# cvocd-a.net
KiCad netlist of a schematic drawn in EAGLE
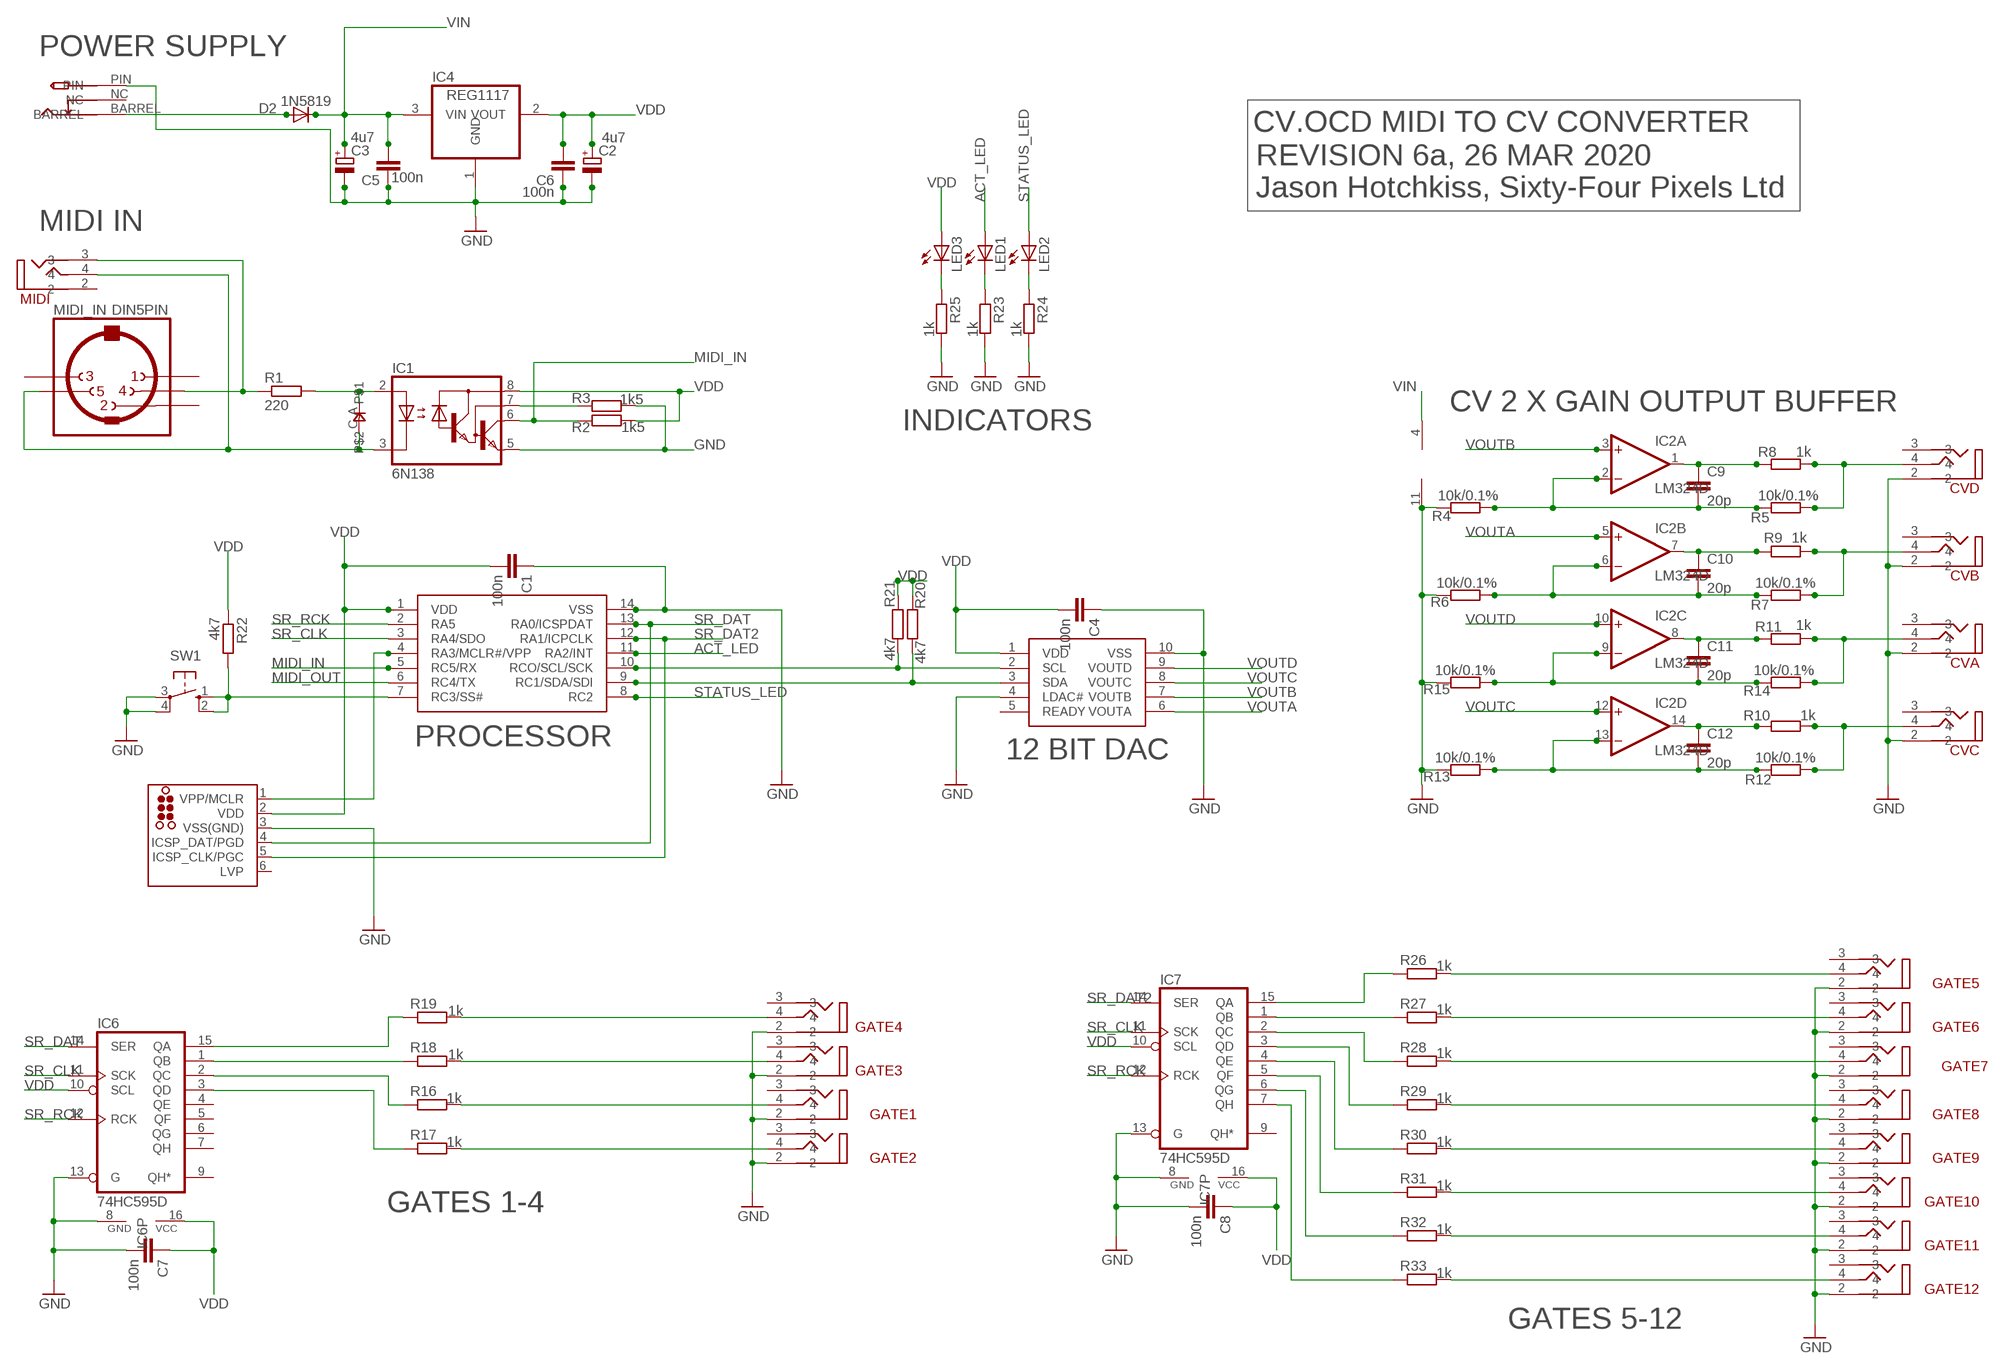
[diagram p0: schematic, sheet 1]

(export (version "E")
  (design (tool "Eeschema 10.0.6"))
  (components
    (comp (ref "C1")
      (value "100n")
      (footprint "eagle-import:C0805")
      (libsource (lib "eagle-import") (part "C-EUC0805"))
    )
    (comp (ref "C2")
      (value "4u7")
      (footprint "eagle-import:PANASONIC_C")
      (libsource (lib "eagle-import") (part "CPOL-EUC"))
    )
    (comp (ref "C3")
      (value "4u7")
      (footprint "eagle-import:PANASONIC_C")
      (libsource (lib "eagle-import") (part "CPOL-EUC"))
    )
    (comp (ref "C4")
      (value "100n")
      (footprint "eagle-import:C0805")
      (libsource (lib "eagle-import") (part "C-EUC0805"))
    )
    (comp (ref "C5")
      (value "100n")
      (footprint "eagle-import:C0805")
      (libsource (lib "eagle-import") (part "C-EUC0805"))
    )
    (comp (ref "C6")
      (value "100n")
      (footprint "eagle-import:C0805")
      (libsource (lib "eagle-import") (part "C-EUC0805"))
    )
    (comp (ref "C7")
      (value "100n")
      (footprint "eagle-import:C0805")
      (libsource (lib "eagle-import") (part "C-EUC0805"))
    )
    (comp (ref "C8")
      (value "100n")
      (footprint "eagle-import:C0805")
      (libsource (lib "eagle-import") (part "C-EUC0805"))
    )
    (comp (ref "C9")
      (value "20p")
      (footprint "eagle-import:C0805")
      (libsource (lib "eagle-import") (part "C-EUC0805"))
    )
    (comp (ref "C10")
      (value "20p")
      (footprint "eagle-import:C0805")
      (libsource (lib "eagle-import") (part "C-EUC0805"))
    )
    (comp (ref "C11")
      (value "20p")
      (footprint "eagle-import:C0805")
      (libsource (lib "eagle-import") (part "C-EUC0805"))
    )
    (comp (ref "C12")
      (value "20p")
      (footprint "eagle-import:C0805")
      (libsource (lib "eagle-import") (part "C-EUC0805"))
    )
    (comp (ref "CVA")
      (value "VERTICAL_3_5MM_SOCKET")
      (footprint "eagle-import:VERTICAL_3_5MM_SOCKET")
      (libsource (lib "eagle-import") (part "VERTICAL_3_5MM_SOCKET"))
    )
    (comp (ref "CVB")
      (value "VERTICAL_3_5MM_SOCKET")
      (footprint "eagle-import:VERTICAL_3_5MM_SOCKET")
      (libsource (lib "eagle-import") (part "VERTICAL_3_5MM_SOCKET"))
    )
    (comp (ref "CVC")
      (value "VERTICAL_3_5MM_SOCKET")
      (footprint "eagle-import:VERTICAL_3_5MM_SOCKET")
      (libsource (lib "eagle-import") (part "VERTICAL_3_5MM_SOCKET"))
    )
    (comp (ref "CVD")
      (value "VERTICAL_3_5MM_SOCKET")
      (footprint "eagle-import:VERTICAL_3_5MM_SOCKET")
      (libsource (lib "eagle-import") (part "VERTICAL_3_5MM_SOCKET"))
    )
    (comp (ref "D1")
      (value "0805DIODE")
      (footprint "eagle-import:0805DIODE")
      (libsource (lib "eagle-import") (part "0805DIODE"))
    )
    (comp (ref "D2")
      (value "1N5819")
      (footprint "eagle-import:SOD123")
      (libsource (lib "eagle-import") (part "DIODE-SOD123"))
    )
    (comp (ref "GATE1")
      (value "VERTICAL_3_5MM_SOCKET")
      (footprint "eagle-import:VERTICAL_3_5MM_SOCKET")
      (libsource (lib "eagle-import") (part "VERTICAL_3_5MM_SOCKET"))
    )
    (comp (ref "GATE2")
      (value "VERTICAL_3_5MM_SOCKET")
      (footprint "eagle-import:VERTICAL_3_5MM_SOCKET")
      (libsource (lib "eagle-import") (part "VERTICAL_3_5MM_SOCKET"))
    )
    (comp (ref "GATE3")
      (value "VERTICAL_3_5MM_SOCKET")
      (footprint "eagle-import:VERTICAL_3_5MM_SOCKET")
      (libsource (lib "eagle-import") (part "VERTICAL_3_5MM_SOCKET"))
    )
    (comp (ref "GATE4")
      (value "VERTICAL_3_5MM_SOCKET")
      (footprint "eagle-import:VERTICAL_3_5MM_SOCKET")
      (libsource (lib "eagle-import") (part "VERTICAL_3_5MM_SOCKET"))
    )
    (comp (ref "GATE5")
      (value "VERTICAL_3_5MM_SOCKET")
      (footprint "eagle-import:VERTICAL_3_5MM_SOCKET")
      (libsource (lib "eagle-import") (part "VERTICAL_3_5MM_SOCKET"))
    )
    (comp (ref "GATE6")
      (value "VERTICAL_3_5MM_SOCKET")
      (footprint "eagle-import:VERTICAL_3_5MM_SOCKET")
      (libsource (lib "eagle-import") (part "VERTICAL_3_5MM_SOCKET"))
    )
    (comp (ref "GATE7")
      (value "VERTICAL_3_5MM_SOCKET")
      (footprint "eagle-import:VERTICAL_3_5MM_SOCKET")
      (libsource (lib "eagle-import") (part "VERTICAL_3_5MM_SOCKET"))
    )
    (comp (ref "GATE8")
      (value "VERTICAL_3_5MM_SOCKET")
      (footprint "eagle-import:VERTICAL_3_5MM_SOCKET")
      (libsource (lib "eagle-import") (part "VERTICAL_3_5MM_SOCKET"))
    )
    (comp (ref "GATE9")
      (value "VERTICAL_3_5MM_SOCKET")
      (footprint "eagle-import:VERTICAL_3_5MM_SOCKET")
      (libsource (lib "eagle-import") (part "VERTICAL_3_5MM_SOCKET"))
    )
    (comp (ref "GATE10")
      (value "VERTICAL_3_5MM_SOCKET")
      (footprint "eagle-import:VERTICAL_3_5MM_SOCKET")
      (libsource (lib "eagle-import") (part "VERTICAL_3_5MM_SOCKET"))
    )
    (comp (ref "GATE11")
      (value "VERTICAL_3_5MM_SOCKET")
      (footprint "eagle-import:VERTICAL_3_5MM_SOCKET")
      (libsource (lib "eagle-import") (part "VERTICAL_3_5MM_SOCKET"))
    )
    (comp (ref "GATE12")
      (value "VERTICAL_3_5MM_SOCKET")
      (footprint "eagle-import:VERTICAL_3_5MM_SOCKET")
      (libsource (lib "eagle-import") (part "VERTICAL_3_5MM_SOCKET"))
    )
    (comp (ref "IC1")
      (value "6N138")
      (footprint "eagle-import:DIL08")
      (fields (field (name "MF") "VISHAY/TELEFUNKEN"))
      (libsource (lib "eagle-import") (part "6N138"))
    )
    (comp (ref "IC2")
      (value "LM324D")
      (footprint "eagle-import:SO14")
      (libsource (lib "eagle-import") (part "LM324D"))
    )
    (comp (ref "IC3")
      (value "MCP4728_QUAD_DAC")
      (footprint "eagle-import:MSOP10")
      (libsource (lib "eagle-import") (part "MCP4728_QUAD_DAC"))
    )
    (comp (ref "IC4")
      (value "REG1117")
      (footprint "eagle-import:SOT223")
      (libsource (lib "eagle-import") (part "REG1117"))
    )
    (comp (ref "IC5")
      (value "PIC16F1825SO14")
      (footprint "eagle-import:SO14")
      (libsource (lib "eagle-import") (part "PIC16F1825SO14"))
    )
    (comp (ref "IC6")
      (value "74HC595D")
      (footprint "eagle-import:SO16")
      (libsource (lib "eagle-import") (part "74595DHC"))
    )
    (comp (ref "IC7")
      (value "74HC595D")
      (footprint "eagle-import:SO16")
      (libsource (lib "eagle-import") (part "74595DHC"))
    )
    (comp (ref "ICSP")
      (value "TC2030-MCP-NL")
      (footprint "eagle-import:TC2030-MCP-NL")
      (libsource (lib "eagle-import") (part "TC2030-MCP-NL"))
    )
    (comp (ref "LED1")
      (value "LED3MM")
      (footprint "eagle-import:LED3MM")
      (libsource (lib "eagle-import") (part "LED3MM"))
    )
    (comp (ref "LED2")
      (value "LED3MM")
      (footprint "eagle-import:LED3MM")
      (libsource (lib "eagle-import") (part "LED3MM"))
    )
    (comp (ref "LED3")
      (value "LED3MM")
      (footprint "eagle-import:LED3MM")
      (libsource (lib "eagle-import") (part "LED3MM"))
    )
    (comp (ref "MIDI")
      (value "VERTICAL_3_5MM_SOCKET")
      (footprint "eagle-import:VERTICAL_3_5MM_SOCKET")
      (libsource (lib "eagle-import") (part "VERTICAL_3_5MM_SOCKET"))
    )
    (comp (ref "MIDI_IN")
      (value "DIN5PIN")
      (footprint "eagle-import:EDGEDIN")
      (libsource (lib "eagle-import") (part "DIN5PIN"))
    )
    (comp (ref "R1")
      (value "220")
      (footprint "eagle-import:R0805")
      (libsource (lib "eagle-import") (part "R-EU_R0805"))
    )
    (comp (ref "R2")
      (value "1k5")
      (footprint "eagle-import:R0805")
      (libsource (lib "eagle-import") (part "R-EU_R0805"))
    )
    (comp (ref "R3")
      (value "1k5")
      (footprint "eagle-import:R0805")
      (libsource (lib "eagle-import") (part "R-EU_R0805"))
    )
    (comp (ref "R4")
      (value "10k/0.1%")
      (footprint "eagle-import:R0805")
      (libsource (lib "eagle-import") (part "R-EU_R0805"))
    )
    (comp (ref "R5")
      (value "10k/0.1%")
      (footprint "eagle-import:R0805")
      (libsource (lib "eagle-import") (part "R-EU_R0805"))
    )
    (comp (ref "R6")
      (value "10k/0.1%")
      (footprint "eagle-import:R0805")
      (libsource (lib "eagle-import") (part "R-EU_R0805"))
    )
    (comp (ref "R7")
      (value "10k/0.1%")
      (footprint "eagle-import:R0805")
      (libsource (lib "eagle-import") (part "R-EU_R0805"))
    )
    (comp (ref "R8")
      (value "1k")
      (footprint "eagle-import:R0805")
      (libsource (lib "eagle-import") (part "R-EU_R0805"))
    )
    (comp (ref "R9")
      (value "1k")
      (footprint "eagle-import:R0805")
      (libsource (lib "eagle-import") (part "R-EU_R0805"))
    )
    (comp (ref "R10")
      (value "1k")
      (footprint "eagle-import:R0805")
      (libsource (lib "eagle-import") (part "R-EU_R0805"))
    )
    (comp (ref "R11")
      (value "1k")
      (footprint "eagle-import:R0805")
      (libsource (lib "eagle-import") (part "R-EU_R0805"))
    )
    (comp (ref "R12")
      (value "10k/0.1%")
      (footprint "eagle-import:R0805")
      (libsource (lib "eagle-import") (part "R-EU_R0805"))
    )
    (comp (ref "R13")
      (value "10k/0.1%")
      (footprint "eagle-import:R0805")
      (libsource (lib "eagle-import") (part "R-EU_R0805"))
    )
    (comp (ref "R14")
      (value "10k/0.1%")
      (footprint "eagle-import:R0805")
      (libsource (lib "eagle-import") (part "R-EU_R0805"))
    )
    (comp (ref "R15")
      (value "10k/0.1%")
      (footprint "eagle-import:R0805")
      (libsource (lib "eagle-import") (part "R-EU_R0805"))
    )
    (comp (ref "R16")
      (value "1k")
      (footprint "eagle-import:R0805")
      (libsource (lib "eagle-import") (part "R-EU_R0805"))
    )
    (comp (ref "R17")
      (value "1k")
      (footprint "eagle-import:R0805")
      (libsource (lib "eagle-import") (part "R-EU_R0805"))
    )
    (comp (ref "R18")
      (value "1k")
      (footprint "eagle-import:R0805")
      (libsource (lib "eagle-import") (part "R-EU_R0805"))
    )
    (comp (ref "R19")
      (value "1k")
      (footprint "eagle-import:R0805")
      (libsource (lib "eagle-import") (part "R-EU_R0805"))
    )
    (comp (ref "R20")
      (value "4k7")
      (footprint "eagle-import:R0805")
      (libsource (lib "eagle-import") (part "R-EU_R0805"))
    )
    (comp (ref "R21")
      (value "4k7")
      (footprint "eagle-import:R0805")
      (libsource (lib "eagle-import") (part "R-EU_R0805"))
    )
    (comp (ref "R22")
      (value "4k7")
      (footprint "eagle-import:R0805")
      (libsource (lib "eagle-import") (part "R-EU_R0805"))
    )
    (comp (ref "R23")
      (value "1k")
      (footprint "eagle-import:R0805")
      (libsource (lib "eagle-import") (part "R-EU_R0805"))
    )
    (comp (ref "R24")
      (value "1k")
      (footprint "eagle-import:R0805")
      (libsource (lib "eagle-import") (part "R-EU_R0805"))
    )
    (comp (ref "R25")
      (value "1k")
      (footprint "eagle-import:R0805")
      (libsource (lib "eagle-import") (part "R-EU_R0805"))
    )
    (comp (ref "R26")
      (value "1k")
      (footprint "eagle-import:R0805")
      (libsource (lib "eagle-import") (part "R-EU_R0805"))
    )
    (comp (ref "R27")
      (value "1k")
      (footprint "eagle-import:R0805")
      (libsource (lib "eagle-import") (part "R-EU_R0805"))
    )
    (comp (ref "R28")
      (value "1k")
      (footprint "eagle-import:R0805")
      (libsource (lib "eagle-import") (part "R-EU_R0805"))
    )
    (comp (ref "R29")
      (value "1k")
      (footprint "eagle-import:R0805")
      (libsource (lib "eagle-import") (part "R-EU_R0805"))
    )
    (comp (ref "R30")
      (value "1k")
      (footprint "eagle-import:R0805")
      (libsource (lib "eagle-import") (part "R-EU_R0805"))
    )
    (comp (ref "R31")
      (value "1k")
      (footprint "eagle-import:R0805")
      (libsource (lib "eagle-import") (part "R-EU_R0805"))
    )
    (comp (ref "R32")
      (value "1k")
      (footprint "eagle-import:R0805")
      (libsource (lib "eagle-import") (part "R-EU_R0805"))
    )
    (comp (ref "R33")
      (value "1k")
      (footprint "eagle-import:R0805")
      (libsource (lib "eagle-import") (part "R-EU_R0805"))
    )
    (comp (ref "SW1")
      (value "10-XX")
      (footprint "eagle-import:B3F-10XX")
      (fields (field (name "MPN") "B3F-1000"))
      (libsource (lib "eagle-import") (part "10-XX"))
    )
    (comp (ref "U$2")
      (value "PWR_SOCKET_2_1MM")
      (footprint "eagle-import:PWR_SOCKET_2_1MM")
      (libsource (lib "eagle-import") (part "PWR_SOCKET_2_1MM"))
    )
  )
  (nets
    (net (code "1") (name "/ACT_LED") (class "Default")
      (node (ref "IC5") (pin "11") (pinfunction "RA2/INT_11") (pintype "bidirectional"))
      (node (ref "LED1") (pin "A") (pinfunction "A_A") (pintype "passive"))
    )
    (net (code "2") (name "/MIDI_IN") (class "Default")
      (node (ref "IC1") (pin "6") (pinfunction "VO_6") (pintype "passive"))
      (node (ref "IC5") (pin "5") (pinfunction "RC5/RX_5") (pintype "bidirectional"))
      (node (ref "R2") (pin "1") (pinfunction "1_1") (pintype "passive"))
    )
    (net (code "3") (name "/MIDI_OUT") (class "Default")
      (node (ref "IC5") (pin "6") (pinfunction "RC4/TX_6") (pintype "bidirectional"))
    )
    (net (code "4") (name "/SR_CLK") (class "Default")
      (node (ref "IC5") (pin "3") (pinfunction "RA4/SDO_3") (pintype "bidirectional"))
      (node (ref "IC6") (pin "11") (pinfunction "SCK_11") (pintype "input"))
      (node (ref "IC7") (pin "11") (pinfunction "SCK_11") (pintype "input"))
    )
    (net (code "5") (name "/SR_DAT") (class "Default")
      (node (ref "IC5") (pin "13") (pinfunction "RA0/ICSPDAT_13") (pintype "bidirectional"))
      (node (ref "IC6") (pin "14") (pinfunction "SER_14") (pintype "input"))
      (node (ref "ICSP") (pin "4") (pinfunction "ICSP_DAT/PGD_4") (pintype "bidirectional"))
    )
    (net (code "6") (name "/SR_DAT2") (class "Default")
      (node (ref "IC5") (pin "12") (pinfunction "RA1/ICPCLK_12") (pintype "bidirectional"))
      (node (ref "IC7") (pin "14") (pinfunction "SER_14") (pintype "input"))
      (node (ref "ICSP") (pin "5") (pinfunction "ICSP_CLK/PGC_5") (pintype "output"))
    )
    (net (code "7") (name "/SR_RCK") (class "Default")
      (node (ref "IC5") (pin "2") (pinfunction "RA5_2") (pintype "bidirectional"))
      (node (ref "IC6") (pin "12") (pinfunction "RCK_12") (pintype "input"))
      (node (ref "IC7") (pin "12") (pinfunction "RCK_12") (pintype "input"))
    )
    (net (code "8") (name "/STATUS_LED") (class "Default")
      (node (ref "IC5") (pin "8") (pinfunction "RC2_8") (pintype "bidirectional"))
      (node (ref "LED2") (pin "A") (pinfunction "A_A") (pintype "passive"))
    )
    (net (code "9") (name "/VDD") (class "Default")
      (node (ref "C1") (pin "2") (pinfunction "2_2") (pintype "passive"))
      (node (ref "C2") (pin "+") (pinfunction "+_+") (pintype "passive"))
      (node (ref "C4") (pin "2") (pinfunction "2_2") (pintype "passive"))
      (node (ref "C6") (pin "2") (pinfunction "2_2") (pintype "passive"))
      (node (ref "C7") (pin "1") (pinfunction "1_1") (pintype "passive"))
      (node (ref "C8") (pin "1") (pinfunction "1_1") (pintype "passive"))
      (node (ref "IC1") (pin "8") (pinfunction "VCC_8") (pintype "passive"))
      (node (ref "IC3") (pin "1") (pinfunction "VDD_1") (pintype "power_in"))
      (node (ref "IC4") (pin "2") (pinfunction "VOUT_2") (pintype "output"))
      (node (ref "IC5") (pin "1") (pinfunction "VDD_1") (pintype "power_in"))
      (node (ref "IC6") (pin "10") (pinfunction "SCL_10") (pintype "input"))
      (node (ref "IC6") (pin "16") (pinfunction "VCC_16") (pintype "power_in"))
      (node (ref "IC7") (pin "10") (pinfunction "SCL_10") (pintype "input"))
      (node (ref "IC7") (pin "16") (pinfunction "VCC_16") (pintype "power_in"))
      (node (ref "ICSP") (pin "2") (pinfunction "VDD_2") (pintype "power_in"))
      (node (ref "LED3") (pin "A") (pinfunction "A_A") (pintype "passive"))
      (node (ref "R2") (pin "2") (pinfunction "2_2") (pintype "passive"))
      (node (ref "R20") (pin "1") (pinfunction "1_1") (pintype "passive"))
      (node (ref "R21") (pin "1") (pinfunction "1_1") (pintype "passive"))
      (node (ref "R22") (pin "1") (pinfunction "1_1") (pintype "passive"))
    )
    (net (code "10") (name "/VIN") (class "Default")
      (node (ref "C3") (pin "+") (pinfunction "+_+") (pintype "passive"))
      (node (ref "C5") (pin "2") (pinfunction "2_2") (pintype "passive"))
      (node (ref "D2") (pin "C") (pinfunction "C_C") (pintype "passive"))
      (node (ref "IC2") (pin "4") (pinfunction "V+_4") (pintype "power_in"))
      (node (ref "IC4") (pin "3") (pinfunction "VIN_3") (pintype "input"))
    )
    (net (code "11") (name "/VOUTA") (class "Default")
      (node (ref "IC2") (pin "5") (pinfunction "+IN_5") (pintype "input"))
      (node (ref "IC3") (pin "6") (pinfunction "VOUTA_6") (pintype "bidirectional"))
    )
    (net (code "12") (name "/VOUTB") (class "Default")
      (node (ref "IC2") (pin "3") (pinfunction "+IN_3") (pintype "input"))
      (node (ref "IC3") (pin "7") (pinfunction "VOUTB_7") (pintype "bidirectional"))
    )
    (net (code "13") (name "/VOUTC") (class "Default")
      (node (ref "IC2") (pin "12") (pinfunction "+IN_12") (pintype "input"))
      (node (ref "IC3") (pin "8") (pinfunction "VOUTC_8") (pintype "bidirectional"))
    )
    (net (code "14") (name "/VOUTD") (class "Default")
      (node (ref "IC2") (pin "10") (pinfunction "+IN_10") (pintype "input"))
      (node (ref "IC3") (pin "9") (pinfunction "VOUTD_9") (pintype "bidirectional"))
    )
    (net (code "15") (name "GND") (class "Default")
      (node (ref "C1") (pin "1") (pinfunction "1_1") (pintype "passive"))
      (node (ref "C2") (pin "-") (pinfunction "-_-") (pintype "passive"))
      (node (ref "C3") (pin "-") (pinfunction "-_-") (pintype "passive"))
      (node (ref "C4") (pin "1") (pinfunction "1_1") (pintype "passive"))
      (node (ref "C5") (pin "1") (pinfunction "1_1") (pintype "passive"))
      (node (ref "C6") (pin "1") (pinfunction "1_1") (pintype "passive"))
      (node (ref "C7") (pin "2") (pinfunction "2_2") (pintype "passive"))
      (node (ref "C8") (pin "2") (pinfunction "2_2") (pintype "passive"))
      (node (ref "CVA") (pin "2") (pinfunction "2_2") (pintype "bidirectional"))
      (node (ref "CVB") (pin "2") (pinfunction "2_2") (pintype "bidirectional"))
      (node (ref "CVC") (pin "2") (pinfunction "2_2") (pintype "bidirectional"))
      (node (ref "CVD") (pin "2") (pinfunction "2_2") (pintype "bidirectional"))
      (node (ref "GATE1") (pin "2") (pinfunction "2_2") (pintype "bidirectional"))
      (node (ref "GATE10") (pin "2") (pinfunction "2_2") (pintype "bidirectional"))
      (node (ref "GATE11") (pin "2") (pinfunction "2_2") (pintype "bidirectional"))
      (node (ref "GATE12") (pin "2") (pinfunction "2_2") (pintype "bidirectional"))
      (node (ref "GATE2") (pin "2") (pinfunction "2_2") (pintype "bidirectional"))
      (node (ref "GATE3") (pin "2") (pinfunction "2_2") (pintype "bidirectional"))
      (node (ref "GATE4") (pin "2") (pinfunction "2_2") (pintype "bidirectional"))
      (node (ref "GATE5") (pin "2") (pinfunction "2_2") (pintype "bidirectional"))
      (node (ref "GATE6") (pin "2") (pinfunction "2_2") (pintype "bidirectional"))
      (node (ref "GATE7") (pin "2") (pinfunction "2_2") (pintype "bidirectional"))
      (node (ref "GATE8") (pin "2") (pinfunction "2_2") (pintype "bidirectional"))
      (node (ref "GATE9") (pin "2") (pinfunction "2_2") (pintype "bidirectional"))
      (node (ref "IC1") (pin "5") (pinfunction "GND_5") (pintype "passive"))
      (node (ref "IC2") (pin "11") (pinfunction "V-_11") (pintype "power_in"))
      (node (ref "IC3") (pin "10") (pinfunction "VSS_10") (pintype "power_in"))
      (node (ref "IC3") (pin "4") (pinfunction "LDAC#_4") (pintype "bidirectional"))
      (node (ref "IC4") (pin "1") (pinfunction "GND_1") (pintype "power_in"))
      (node (ref "IC5") (pin "14") (pinfunction "VSS_14") (pintype "power_in"))
      (node (ref "IC6") (pin "13") (pinfunction "G_13") (pintype "input"))
      (node (ref "IC6") (pin "8") (pinfunction "GND_8") (pintype "power_in"))
      (node (ref "IC7") (pin "13") (pinfunction "G_13") (pintype "input"))
      (node (ref "IC7") (pin "8") (pinfunction "GND_8") (pintype "power_in"))
      (node (ref "ICSP") (pin "3") (pinfunction "VSS(GND)_3") (pintype "power_in"))
      (node (ref "R13") (pin "1") (pinfunction "1_1") (pintype "passive"))
      (node (ref "R15") (pin "1") (pinfunction "1_1") (pintype "passive"))
      (node (ref "R23") (pin "2") (pinfunction "2_2") (pintype "passive"))
      (node (ref "R24") (pin "2") (pinfunction "2_2") (pintype "passive"))
      (node (ref "R25") (pin "2") (pinfunction "2_2") (pintype "passive"))
      (node (ref "R3") (pin "2") (pinfunction "2_2") (pintype "passive"))
      (node (ref "R4") (pin "1") (pinfunction "1_1") (pintype "passive"))
      (node (ref "R6") (pin "1") (pinfunction "1_1") (pintype "passive"))
      (node (ref "SW1") (pin "3") (pinfunction "P_3") (pintype "passive"))
      (node (ref "SW1") (pin "4") (pinfunction "P1_4") (pintype "passive"))
      (node (ref "U$2") (pin "PIN") (pinfunction "PIN_PIN") (pintype "bidirectional"))
    )
    (net (code "16") (name "Net-(CVA-Pad4)") (class "Default")
      (node (ref "CVA") (pin "4") (pinfunction "4_4") (pintype "bidirectional"))
      (node (ref "R11") (pin "2") (pinfunction "2_2") (pintype "passive"))
      (node (ref "R14") (pin "2") (pinfunction "2_2") (pintype "passive"))
    )
    (net (code "17") (name "Net-(CVB-Pad4)") (class "Default")
      (node (ref "CVB") (pin "4") (pinfunction "4_4") (pintype "bidirectional"))
      (node (ref "R7") (pin "2") (pinfunction "2_2") (pintype "passive"))
      (node (ref "R9") (pin "2") (pinfunction "2_2") (pintype "passive"))
    )
    (net (code "18") (name "Net-(CVC-Pad4)") (class "Default")
      (node (ref "CVC") (pin "4") (pinfunction "4_4") (pintype "bidirectional"))
      (node (ref "R10") (pin "2") (pinfunction "2_2") (pintype "passive"))
      (node (ref "R12") (pin "2") (pinfunction "2_2") (pintype "passive"))
    )
    (net (code "19") (name "Net-(CVD-Pad4)") (class "Default")
      (node (ref "CVD") (pin "4") (pinfunction "4_4") (pintype "bidirectional"))
      (node (ref "R5") (pin "2") (pinfunction "2_2") (pintype "passive"))
      (node (ref "R8") (pin "2") (pinfunction "2_2") (pintype "passive"))
    )
    (net (code "20") (name "Net-(D1-P$1)") (class "Default")
      (node (ref "D1") (pin "C") (pinfunction "P$1_C") (pintype "bidirectional"))
      (node (ref "IC1") (pin "3") (pinfunction "C_3") (pintype "passive"))
      (node (ref "MIDI") (pin "4") (pinfunction "4_4") (pintype "bidirectional"))
      (node (ref "MIDI_IN") (pin "5") (pinfunction "5_5") (pintype "passive"))
    )
    (net (code "21") (name "Net-(D1-P$2)") (class "Default")
      (node (ref "D1") (pin "A") (pinfunction "P$2_A") (pintype "bidirectional"))
      (node (ref "IC1") (pin "2") (pinfunction "A_2") (pintype "passive"))
      (node (ref "R1") (pin "2") (pinfunction "2_2") (pintype "passive"))
    )
    (net (code "22") (name "Net-(D2-PadA)") (class "Default")
      (node (ref "D2") (pin "A") (pinfunction "A_A") (pintype "passive"))
      (node (ref "U$2") (pin "BARREL") (pinfunction "BARREL_BARREL") (pintype "bidirectional"))
    )
    (net (code "23") (name "Net-(GATE1-Pad4)") (class "Default")
      (node (ref "GATE1") (pin "4") (pinfunction "4_4") (pintype "bidirectional"))
      (node (ref "R16") (pin "2") (pinfunction "2_2") (pintype "passive"))
    )
    (net (code "24") (name "Net-(GATE2-Pad4)") (class "Default")
      (node (ref "GATE2") (pin "4") (pinfunction "4_4") (pintype "bidirectional"))
      (node (ref "R17") (pin "2") (pinfunction "2_2") (pintype "passive"))
    )
    (net (code "25") (name "Net-(GATE3-Pad4)") (class "Default")
      (node (ref "GATE3") (pin "4") (pinfunction "4_4") (pintype "bidirectional"))
      (node (ref "R18") (pin "2") (pinfunction "2_2") (pintype "passive"))
    )
    (net (code "26") (name "Net-(GATE4-Pad4)") (class "Default")
      (node (ref "GATE4") (pin "4") (pinfunction "4_4") (pintype "bidirectional"))
      (node (ref "R19") (pin "2") (pinfunction "2_2") (pintype "passive"))
    )
    (net (code "27") (name "Net-(GATE5-Pad4)") (class "Default")
      (node (ref "GATE5") (pin "4") (pinfunction "4_4") (pintype "bidirectional"))
      (node (ref "R26") (pin "2") (pinfunction "2_2") (pintype "passive"))
    )
    (net (code "28") (name "Net-(GATE6-Pad4)") (class "Default")
      (node (ref "GATE6") (pin "4") (pinfunction "4_4") (pintype "bidirectional"))
      (node (ref "R27") (pin "2") (pinfunction "2_2") (pintype "passive"))
    )
    (net (code "29") (name "Net-(GATE7-Pad4)") (class "Default")
      (node (ref "GATE7") (pin "4") (pinfunction "4_4") (pintype "bidirectional"))
      (node (ref "R28") (pin "2") (pinfunction "2_2") (pintype "passive"))
    )
    (net (code "30") (name "Net-(GATE8-Pad4)") (class "Default")
      (node (ref "GATE8") (pin "4") (pinfunction "4_4") (pintype "bidirectional"))
      (node (ref "R29") (pin "2") (pinfunction "2_2") (pintype "passive"))
    )
    (net (code "31") (name "Net-(GATE9-Pad4)") (class "Default")
      (node (ref "GATE9") (pin "4") (pinfunction "4_4") (pintype "bidirectional"))
      (node (ref "R30") (pin "2") (pinfunction "2_2") (pintype "passive"))
    )
    (net (code "32") (name "Net-(GATE10-Pad4)") (class "Default")
      (node (ref "GATE10") (pin "4") (pinfunction "4_4") (pintype "bidirectional"))
      (node (ref "R31") (pin "2") (pinfunction "2_2") (pintype "passive"))
    )
    (net (code "33") (name "Net-(GATE11-Pad4)") (class "Default")
      (node (ref "GATE11") (pin "4") (pinfunction "4_4") (pintype "bidirectional"))
      (node (ref "R32") (pin "2") (pinfunction "2_2") (pintype "passive"))
    )
    (net (code "34") (name "Net-(GATE12-Pad4)") (class "Default")
      (node (ref "GATE12") (pin "4") (pinfunction "4_4") (pintype "bidirectional"))
      (node (ref "R33") (pin "2") (pinfunction "2_2") (pintype "passive"))
    )
    (net (code "35") (name "Net-(IC1-VB)") (class "Default")
      (node (ref "IC1") (pin "7") (pinfunction "VB_7") (pintype "passive"))
      (node (ref "R3") (pin "1") (pinfunction "1_1") (pintype "passive"))
    )
    (net (code "36") (name "Net-(IC2A--IN)") (class "Default")
      (node (ref "C9") (pin "2") (pinfunction "2_2") (pintype "passive"))
      (node (ref "IC2") (pin "2") (pinfunction "-IN_2") (pintype "input"))
      (node (ref "R4") (pin "2") (pinfunction "2_2") (pintype "passive"))
      (node (ref "R5") (pin "1") (pinfunction "1_1") (pintype "passive"))
    )
    (net (code "37") (name "Net-(IC2A-OUT)") (class "Default")
      (node (ref "C9") (pin "1") (pinfunction "1_1") (pintype "passive"))
      (node (ref "IC2") (pin "1") (pinfunction "OUT_1") (pintype "output"))
      (node (ref "R8") (pin "1") (pinfunction "1_1") (pintype "passive"))
    )
    (net (code "38") (name "Net-(IC2B--IN)") (class "Default")
      (node (ref "C10") (pin "2") (pinfunction "2_2") (pintype "passive"))
      (node (ref "IC2") (pin "6") (pinfunction "-IN_6") (pintype "input"))
      (node (ref "R6") (pin "2") (pinfunction "2_2") (pintype "passive"))
      (node (ref "R7") (pin "1") (pinfunction "1_1") (pintype "passive"))
    )
    (net (code "39") (name "Net-(IC2B-OUT)") (class "Default")
      (node (ref "C10") (pin "1") (pinfunction "1_1") (pintype "passive"))
      (node (ref "IC2") (pin "7") (pinfunction "OUT_7") (pintype "output"))
      (node (ref "R9") (pin "1") (pinfunction "1_1") (pintype "passive"))
    )
    (net (code "40") (name "Net-(IC2C--IN)") (class "Default")
      (node (ref "C11") (pin "2") (pinfunction "2_2") (pintype "passive"))
      (node (ref "IC2") (pin "9") (pinfunction "-IN_9") (pintype "input"))
      (node (ref "R14") (pin "1") (pinfunction "1_1") (pintype "passive"))
      (node (ref "R15") (pin "2") (pinfunction "2_2") (pintype "passive"))
    )
    (net (code "41") (name "Net-(IC2C-OUT)") (class "Default")
      (node (ref "C11") (pin "1") (pinfunction "1_1") (pintype "passive"))
      (node (ref "IC2") (pin "8") (pinfunction "OUT_8") (pintype "output"))
      (node (ref "R11") (pin "1") (pinfunction "1_1") (pintype "passive"))
    )
    (net (code "42") (name "Net-(IC2D--IN)") (class "Default")
      (node (ref "C12") (pin "2") (pinfunction "2_2") (pintype "passive"))
      (node (ref "IC2") (pin "13") (pinfunction "-IN_13") (pintype "input"))
      (node (ref "R12") (pin "1") (pinfunction "1_1") (pintype "passive"))
      (node (ref "R13") (pin "2") (pinfunction "2_2") (pintype "passive"))
    )
    (net (code "43") (name "Net-(IC2D-OUT)") (class "Default")
      (node (ref "C12") (pin "1") (pinfunction "1_1") (pintype "passive"))
      (node (ref "IC2") (pin "14") (pinfunction "OUT_14") (pintype "output"))
      (node (ref "R10") (pin "1") (pinfunction "1_1") (pintype "passive"))
    )
    (net (code "44") (name "Net-(IC3-SCL)") (class "Default")
      (node (ref "IC3") (pin "2") (pinfunction "SCL_2") (pintype "bidirectional"))
      (node (ref "IC5") (pin "10") (pinfunction "RCO/SCL/SCK_10") (pintype "bidirectional"))
      (node (ref "R21") (pin "2") (pinfunction "2_2") (pintype "passive"))
    )
    (net (code "45") (name "Net-(IC3-SDA)") (class "Default")
      (node (ref "IC3") (pin "3") (pinfunction "SDA_3") (pintype "bidirectional"))
      (node (ref "IC5") (pin "9") (pinfunction "RC1/SDA/SDI_9") (pintype "bidirectional"))
      (node (ref "R20") (pin "2") (pinfunction "2_2") (pintype "passive"))
    )
    (net (code "46") (name "Net-(IC5-RA3{slash}MCLR#{slash}VPP)") (class "Default")
      (node (ref "IC5") (pin "4") (pinfunction "RA3/MCLR#/VPP_4") (pintype "input"))
      (node (ref "ICSP") (pin "1") (pinfunction "VPP/MCLR_1") (pintype "passive"))
    )
    (net (code "47") (name "Net-(IC5-RC3{slash}SS#)") (class "Default")
      (node (ref "IC5") (pin "7") (pinfunction "RC3/SS#_7") (pintype "bidirectional"))
      (node (ref "R22") (pin "2") (pinfunction "2_2") (pintype "passive"))
      (node (ref "SW1") (pin "1") (pinfunction "S_1") (pintype "passive"))
      (node (ref "SW1") (pin "2") (pinfunction "S1_2") (pintype "passive"))
    )
    (net (code "48") (name "Net-(IC6A-QA)") (class "Default")
      (node (ref "IC6") (pin "15") (pinfunction "QA_15") (pintype "tri_state"))
      (node (ref "R19") (pin "1") (pinfunction "1_1") (pintype "passive"))
    )
    (net (code "49") (name "Net-(IC6A-QB)") (class "Default")
      (node (ref "IC6") (pin "1") (pinfunction "QB_1") (pintype "tri_state"))
      (node (ref "R18") (pin "1") (pinfunction "1_1") (pintype "passive"))
    )
    (net (code "50") (name "Net-(IC6A-QC)") (class "Default")
      (node (ref "IC6") (pin "2") (pinfunction "QC_2") (pintype "tri_state"))
      (node (ref "R16") (pin "1") (pinfunction "1_1") (pintype "passive"))
    )
    (net (code "51") (name "Net-(IC6A-QD)") (class "Default")
      (node (ref "IC6") (pin "3") (pinfunction "QD_3") (pintype "tri_state"))
      (node (ref "R17") (pin "1") (pinfunction "1_1") (pintype "passive"))
    )
    (net (code "52") (name "Net-(IC7A-QA)") (class "Default")
      (node (ref "IC7") (pin "15") (pinfunction "QA_15") (pintype "tri_state"))
      (node (ref "R26") (pin "1") (pinfunction "1_1") (pintype "passive"))
    )
    (net (code "53") (name "Net-(IC7A-QB)") (class "Default")
      (node (ref "IC7") (pin "1") (pinfunction "QB_1") (pintype "tri_state"))
      (node (ref "R27") (pin "1") (pinfunction "1_1") (pintype "passive"))
    )
    (net (code "54") (name "Net-(IC7A-QC)") (class "Default")
      (node (ref "IC7") (pin "2") (pinfunction "QC_2") (pintype "tri_state"))
      (node (ref "R28") (pin "1") (pinfunction "1_1") (pintype "passive"))
    )
    (net (code "55") (name "Net-(IC7A-QD)") (class "Default")
      (node (ref "IC7") (pin "3") (pinfunction "QD_3") (pintype "tri_state"))
      (node (ref "R29") (pin "1") (pinfunction "1_1") (pintype "passive"))
    )
    (net (code "56") (name "Net-(IC7A-QE)") (class "Default")
      (node (ref "IC7") (pin "4") (pinfunction "QE_4") (pintype "tri_state"))
      (node (ref "R30") (pin "1") (pinfunction "1_1") (pintype "passive"))
    )
    (net (code "57") (name "Net-(IC7A-QF)") (class "Default")
      (node (ref "IC7") (pin "5") (pinfunction "QF_5") (pintype "tri_state"))
      (node (ref "R31") (pin "1") (pinfunction "1_1") (pintype "passive"))
    )
    (net (code "58") (name "Net-(IC7A-QG)") (class "Default")
      (node (ref "IC7") (pin "6") (pinfunction "QG_6") (pintype "tri_state"))
      (node (ref "R32") (pin "1") (pinfunction "1_1") (pintype "passive"))
    )
    (net (code "59") (name "Net-(IC7A-QH)") (class "Default")
      (node (ref "IC7") (pin "7") (pinfunction "QH_7") (pintype "tri_state"))
      (node (ref "R33") (pin "1") (pinfunction "1_1") (pintype "passive"))
    )
    (net (code "60") (name "Net-(LED1-C)") (class "Default")
      (node (ref "LED1") (pin "K") (pinfunction "C_K") (pintype "passive"))
      (node (ref "R23") (pin "1") (pinfunction "1_1") (pintype "passive"))
    )
    (net (code "61") (name "Net-(LED2-C)") (class "Default")
      (node (ref "LED2") (pin "K") (pinfunction "C_K") (pintype "passive"))
      (node (ref "R24") (pin "1") (pinfunction "1_1") (pintype "passive"))
    )
    (net (code "62") (name "Net-(LED3-C)") (class "Default")
      (node (ref "LED3") (pin "K") (pinfunction "C_K") (pintype "passive"))
      (node (ref "R25") (pin "1") (pinfunction "1_1") (pintype "passive"))
    )
    (net (code "63") (name "Net-(MIDI-Pad3)") (class "Default")
      (node (ref "MIDI") (pin "3") (pinfunction "3_3") (pintype "bidirectional"))
      (node (ref "MIDI_IN") (pin "4") (pinfunction "4_4") (pintype "passive"))
      (node (ref "R1") (pin "1") (pinfunction "1_1") (pintype "passive"))
    )
    (net (code "64") (name "unconnected-(CVA-Pad3)") (class "Default")
      (node (ref "CVA") (pin "3") (pinfunction "3_3") (pintype "bidirectional"))
    )
    (net (code "65") (name "unconnected-(CVB-Pad3)") (class "Default")
      (node (ref "CVB") (pin "3") (pinfunction "3_3") (pintype "bidirectional"))
    )
    (net (code "66") (name "unconnected-(CVC-Pad3)") (class "Default")
      (node (ref "CVC") (pin "3") (pinfunction "3_3") (pintype "bidirectional"))
    )
    (net (code "67") (name "unconnected-(CVD-Pad3)") (class "Default")
      (node (ref "CVD") (pin "3") (pinfunction "3_3") (pintype "bidirectional"))
    )
    (net (code "68") (name "unconnected-(GATE1-Pad3)") (class "Default")
      (node (ref "GATE1") (pin "3") (pinfunction "3_3") (pintype "bidirectional"))
    )
    (net (code "69") (name "unconnected-(GATE2-Pad3)") (class "Default")
      (node (ref "GATE2") (pin "3") (pinfunction "3_3") (pintype "bidirectional"))
    )
    (net (code "70") (name "unconnected-(GATE3-Pad3)") (class "Default")
      (node (ref "GATE3") (pin "3") (pinfunction "3_3") (pintype "bidirectional"))
    )
    (net (code "71") (name "unconnected-(GATE4-Pad3)") (class "Default")
      (node (ref "GATE4") (pin "3") (pinfunction "3_3") (pintype "bidirectional"))
    )
    (net (code "72") (name "unconnected-(GATE5-Pad3)") (class "Default")
      (node (ref "GATE5") (pin "3") (pinfunction "3_3") (pintype "bidirectional"))
    )
    (net (code "73") (name "unconnected-(GATE6-Pad3)") (class "Default")
      (node (ref "GATE6") (pin "3") (pinfunction "3_3") (pintype "bidirectional"))
    )
    (net (code "74") (name "unconnected-(GATE7-Pad3)") (class "Default")
      (node (ref "GATE7") (pin "3") (pinfunction "3_3") (pintype "bidirectional"))
    )
    (net (code "75") (name "unconnected-(GATE8-Pad3)") (class "Default")
      (node (ref "GATE8") (pin "3") (pinfunction "3_3") (pintype "bidirectional"))
    )
    (net (code "76") (name "unconnected-(GATE9-Pad3)") (class "Default")
      (node (ref "GATE9") (pin "3") (pinfunction "3_3") (pintype "bidirectional"))
    )
    (net (code "77") (name "unconnected-(GATE10-Pad3)") (class "Default")
      (node (ref "GATE10") (pin "3") (pinfunction "3_3") (pintype "bidirectional"))
    )
    (net (code "78") (name "unconnected-(GATE11-Pad3)") (class "Default")
      (node (ref "GATE11") (pin "3") (pinfunction "3_3") (pintype "bidirectional"))
    )
    (net (code "79") (name "unconnected-(GATE12-Pad3)") (class "Default")
      (node (ref "GATE12") (pin "3") (pinfunction "3_3") (pintype "bidirectional"))
    )
    (net (code "80") (name "unconnected-(IC3-READY-Pad5)") (class "Default")
      (node (ref "IC3") (pin "5") (pinfunction "READY_5") (pintype "bidirectional"))
    )
    (net (code "81") (name "unconnected-(IC6A-QE-Pad4)") (class "Default")
      (node (ref "IC6") (pin "4") (pinfunction "QE_4") (pintype "tri_state"))
    )
    (net (code "82") (name "unconnected-(IC6A-QF-Pad5)") (class "Default")
      (node (ref "IC6") (pin "5") (pinfunction "QF_5") (pintype "tri_state"))
    )
    (net (code "83") (name "unconnected-(IC6A-QG-Pad6)") (class "Default")
      (node (ref "IC6") (pin "6") (pinfunction "QG_6") (pintype "tri_state"))
    )
    (net (code "84") (name "unconnected-(IC6A-QH*-Pad9)") (class "Default")
      (node (ref "IC6") (pin "9") (pinfunction "QH*_9") (pintype "tri_state"))
    )
    (net (code "85") (name "unconnected-(IC6A-QH-Pad7)") (class "Default")
      (node (ref "IC6") (pin "7") (pinfunction "QH_7") (pintype "tri_state"))
    )
    (net (code "86") (name "unconnected-(IC7A-QH*-Pad9)") (class "Default")
      (node (ref "IC7") (pin "9") (pinfunction "QH*_9") (pintype "tri_state"))
    )
    (net (code "87") (name "unconnected-(ICSP-LVP-Pad6)") (class "Default")
      (node (ref "ICSP") (pin "6") (pinfunction "LVP_6") (pintype "bidirectional"))
    )
    (net (code "88") (name "unconnected-(MIDI-Pad2)") (class "Default")
      (node (ref "MIDI") (pin "2") (pinfunction "2_2") (pintype "bidirectional"))
    )
    (net (code "89") (name "unconnected-(MIDI_IN-Pad1)") (class "Default")
      (node (ref "MIDI_IN") (pin "1") (pinfunction "1_1") (pintype "passive"))
    )
    (net (code "90") (name "unconnected-(MIDI_IN-Pad2)") (class "Default")
      (node (ref "MIDI_IN") (pin "2") (pinfunction "2_2") (pintype "passive"))
    )
    (net (code "91") (name "unconnected-(MIDI_IN-Pad3)") (class "Default")
      (node (ref "MIDI_IN") (pin "3") (pinfunction "3_3") (pintype "passive"))
    )
    (net (code "92") (name "unconnected-(U$2-PadNC)") (class "Default")
      (node (ref "U$2") (pin "NC") (pinfunction "NC_NC") (pintype "bidirectional"))
    )
  )
)
